# vescom.net
KiCad netlist of a schematic drawn in EAGLE
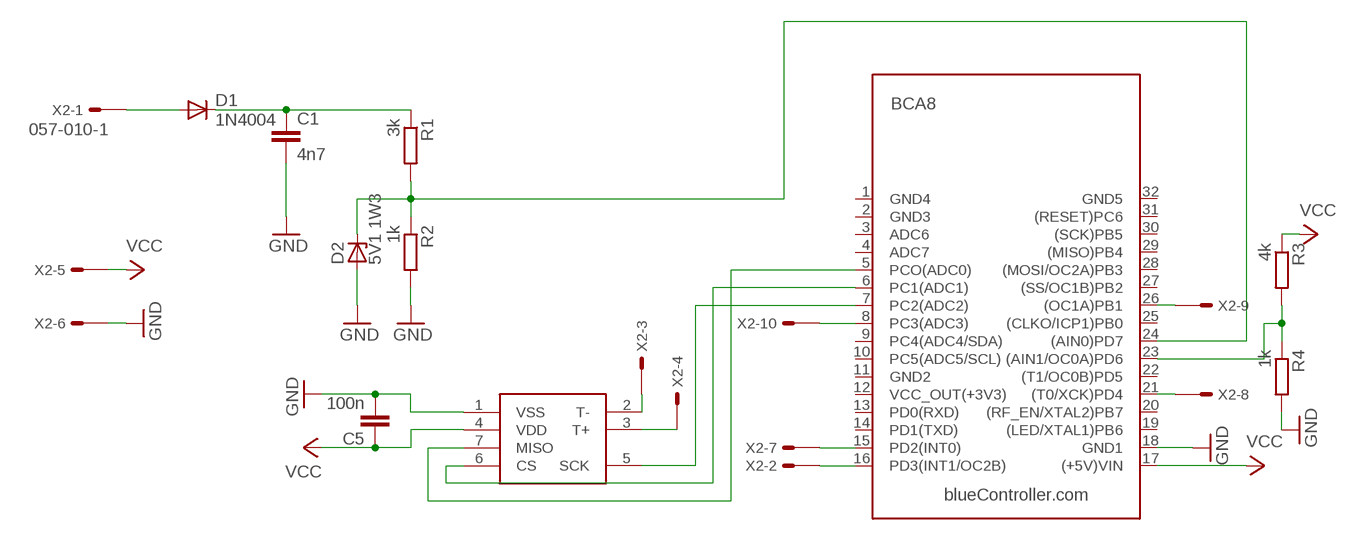
[diagram p0: schematic, sheet 1]

(export (version "E")
  (design (tool "Eeschema 10.0.6"))
  (components
    (comp (ref "C1")
      (value "4n7")
      (footprint "eagle-import:C025-025X050")
      (libsource (lib "eagle-import") (part "C-EU025-025X050"))
    )
    (comp (ref "C5")
      (value "100n")
      (footprint "eagle-import:C025-025X050")
      (libsource (lib "eagle-import") (part "C-EU025-025X050"))
    )
    (comp (ref "D1")
      (value "1N4004")
      (footprint "eagle-import:DO41-10")
      (libsource (lib "eagle-import") (part "1N4004"))
    )
    (comp (ref "D2")
      (value "5V1 1W3")
      (footprint "eagle-import:DO34Z7")
      (libsource (lib "eagle-import") (part "ZENER-DIODEDO34-7"))
    )
    (comp (ref "MAX6675")
      (value "MAX6675")
      (footprint "eagle-import:SO08")
      (libsource (lib "eagle-import") (part "MAX6675"))
    )
    (comp (ref "R1")
      (value "3k")
      (footprint "eagle-import:0207_10")
      (libsource (lib "eagle-import") (part "R-EU_0207/10"))
    )
    (comp (ref "R2")
      (value "1k")
      (footprint "eagle-import:0207_10")
      (libsource (lib "eagle-import") (part "R-EU_0207/10"))
    )
    (comp (ref "R3")
      (value "4k")
      (footprint "eagle-import:0207_10")
      (libsource (lib "eagle-import") (part "R-EU_0207/10"))
    )
    (comp (ref "R4")
      (value "1k")
      (footprint "eagle-import:0207_10")
      (libsource (lib "eagle-import") (part "R-EU_0207/10"))
    )
    (comp (ref "U$1") (value "BC") (footprint "eagle-import:BC") (libsource (lib "eagle-import") (part "BC")))
    (comp (ref "X2")
      (value "057-010-1")
      (footprint "eagle-import:057-010-1")
      (libsource (lib "eagle-import") (part "057-010-1"))
    )
  )
  (nets
    (net (code "1") (name "GND") (class "Default")
      (node (ref "C1") (pin "2") (pinfunction "2_2") (pintype "passive"))
      (node (ref "C5") (pin "2") (pinfunction "2_2") (pintype "passive"))
      (node (ref "D2") (pin "A") (pinfunction "A_A") (pintype "passive"))
      (node (ref "MAX6675") (pin "1") (pinfunction "VSS_1") (pintype "bidirectional"))
      (node (ref "R2") (pin "2") (pinfunction "2_2") (pintype "passive"))
      (node (ref "R4") (pin "2") (pinfunction "2_2") (pintype "passive"))
      (node (ref "U$1") (pin "18") (pinfunction "GND1_18") (pintype "bidirectional"))
      (node (ref "X2") (pin "6") (pinfunction "S_6") (pintype "passive"))
    )
    (net (code "2") (name "Net-(C1-Pad1)") (class "Default")
      (node (ref "C1") (pin "1") (pinfunction "1_1") (pintype "passive"))
      (node (ref "D1") (pin "C") (pinfunction "C_C") (pintype "passive"))
      (node (ref "R1") (pin "1") (pinfunction "1_1") (pintype "passive"))
    )
    (net (code "3") (name "Net-(MAX6675-CS)") (class "Default")
      (node (ref "MAX6675") (pin "6") (pinfunction "CS_6") (pintype "bidirectional"))
      (node (ref "U$1") (pin "6") (pinfunction "PC1(ADC1)_6") (pintype "bidirectional"))
    )
    (net (code "4") (name "Net-(MAX6675-MISO)") (class "Default")
      (node (ref "MAX6675") (pin "7") (pinfunction "MISO_7") (pintype "bidirectional"))
      (node (ref "U$1") (pin "5") (pinfunction "PCO(ADC0)_5") (pintype "bidirectional"))
    )
    (net (code "5") (name "Net-(MAX6675-SCK)") (class "Default")
      (node (ref "MAX6675") (pin "5") (pinfunction "SCK_5") (pintype "bidirectional"))
      (node (ref "U$1") (pin "7") (pinfunction "PC2(ADC2)_7") (pintype "bidirectional"))
    )
    (net (code "6") (name "Net-(MAX6675-T+)") (class "Default")
      (node (ref "MAX6675") (pin "3") (pinfunction "T+_3") (pintype "bidirectional"))
      (node (ref "X2") (pin "4") (pinfunction "S_4") (pintype "passive"))
    )
    (net (code "7") (name "Net-(MAX6675-T-)") (class "Default")
      (node (ref "MAX6675") (pin "2") (pinfunction "T-_2") (pintype "bidirectional"))
      (node (ref "X2") (pin "3") (pinfunction "S_3") (pintype "passive"))
    )
    (net (code "8") (name "Net-(U$1-(AIN0)PD7)") (class "Default")
      (node (ref "D2") (pin "C") (pinfunction "C_C") (pintype "passive"))
      (node (ref "R1") (pin "2") (pinfunction "2_2") (pintype "passive"))
      (node (ref "R2") (pin "1") (pinfunction "1_1") (pintype "passive"))
      (node (ref "U$1") (pin "24") (pinfunction "(AIN0)PD7_24") (pintype "bidirectional"))
    )
    (net (code "9") (name "Net-(U$1-(AIN1{slash}OC0A)PD6)") (class "Default")
      (node (ref "R3") (pin "2") (pinfunction "2_2") (pintype "passive"))
      (node (ref "R4") (pin "1") (pinfunction "1_1") (pintype "passive"))
      (node (ref "U$1") (pin "23") (pinfunction "(AIN1/OC0A)PD6_23") (pintype "bidirectional"))
    )
    (net (code "10") (name "Net-(U$1-(OC1A)PB1)") (class "Default")
      (node (ref "U$1") (pin "26") (pinfunction "(OC1A)PB1_26") (pintype "bidirectional"))
      (node (ref "X2") (pin "9") (pinfunction "S_9") (pintype "passive"))
    )
    (net (code "11") (name "Net-(U$1-(T0{slash}XCK)PD4)") (class "Default")
      (node (ref "U$1") (pin "21") (pinfunction "(T0/XCK)PD4_21") (pintype "bidirectional"))
      (node (ref "X2") (pin "8") (pinfunction "S_8") (pintype "passive"))
    )
    (net (code "12") (name "Net-(U$1-PC3(ADC3))") (class "Default")
      (node (ref "U$1") (pin "8") (pinfunction "PC3(ADC3)_8") (pintype "bidirectional"))
      (node (ref "X2") (pin "10") (pinfunction "S_10") (pintype "passive"))
    )
    (net (code "13") (name "Net-(U$1-PD2(INT0))") (class "Default")
      (node (ref "U$1") (pin "15") (pinfunction "PD2(INT0)_15") (pintype "bidirectional"))
      (node (ref "X2") (pin "7") (pinfunction "S_7") (pintype "passive"))
    )
    (net (code "14") (name "Net-(U$1-PD3(INT1{slash}OC2B))") (class "Default")
      (node (ref "U$1") (pin "16") (pinfunction "PD3(INT1/OC2B)_16") (pintype "bidirectional"))
      (node (ref "X2") (pin "2") (pinfunction "S_2") (pintype "passive"))
    )
    (net (code "15") (name "Net-(X2A-S)") (class "Default")
      (node (ref "D1") (pin "A") (pinfunction "A_A") (pintype "passive"))
      (node (ref "X2") (pin "1") (pinfunction "S_1") (pintype "passive"))
    )
    (net (code "16") (name "VCC") (class "Default")
      (node (ref "C5") (pin "1") (pinfunction "1_1") (pintype "passive"))
      (node (ref "MAX6675") (pin "4") (pinfunction "VDD_4") (pintype "bidirectional"))
      (node (ref "R3") (pin "1") (pinfunction "1_1") (pintype "passive"))
      (node (ref "U$1") (pin "17") (pinfunction "(+5V)VIN_17") (pintype "bidirectional"))
      (node (ref "X2") (pin "5") (pinfunction "S_5") (pintype "passive"))
    )
    (net (code "17") (name "unconnected-(U$1-(CLKO{slash}ICP1)PB0-Pad25)") (class "Default")
      (node (ref "U$1") (pin "25") (pinfunction "(CLKO/ICP1)PB0_25") (pintype "bidirectional"))
    )
    (net (code "18") (name "unconnected-(U$1-(LED{slash}XTAL1)PB6-Pad19)") (class "Default")
      (node (ref "U$1") (pin "19") (pinfunction "(LED/XTAL1)PB6_19") (pintype "bidirectional"))
    )
    (net (code "19") (name "unconnected-(U$1-(MISO)PB4-Pad29)") (class "Default")
      (node (ref "U$1") (pin "29") (pinfunction "(MISO)PB4_29") (pintype "bidirectional"))
    )
    (net (code "20") (name "unconnected-(U$1-(MOSI{slash}OC2A)PB3-Pad28)") (class "Default")
      (node (ref "U$1") (pin "28") (pinfunction "(MOSI/OC2A)PB3_28") (pintype "bidirectional"))
    )
    (net (code "21") (name "unconnected-(U$1-(RESET)PC6-Pad31)") (class "Default")
      (node (ref "U$1") (pin "31") (pinfunction "(RESET)PC6_31") (pintype "bidirectional"))
    )
    (net (code "22") (name "unconnected-(U$1-(RF_EN{slash}XTAL2)PB7-Pad20)") (class "Default")
      (node (ref "U$1") (pin "20") (pinfunction "(RF_EN/XTAL2)PB7_20") (pintype "bidirectional"))
    )
    (net (code "23") (name "unconnected-(U$1-(SCK)PB5-Pad30)") (class "Default")
      (node (ref "U$1") (pin "30") (pinfunction "(SCK)PB5_30") (pintype "bidirectional"))
    )
    (net (code "24") (name "unconnected-(U$1-(SS{slash}OC1B)PB2-Pad27)") (class "Default")
      (node (ref "U$1") (pin "27") (pinfunction "(SS/OC1B)PB2_27") (pintype "bidirectional"))
    )
    (net (code "25") (name "unconnected-(U$1-(T1{slash}OC0B)PD5-Pad22)") (class "Default")
      (node (ref "U$1") (pin "22") (pinfunction "(T1/OC0B)PD5_22") (pintype "bidirectional"))
    )
    (net (code "26") (name "unconnected-(U$1-ADC6-Pad3)") (class "Default")
      (node (ref "U$1") (pin "3") (pinfunction "ADC6_3") (pintype "bidirectional"))
    )
    (net (code "27") (name "unconnected-(U$1-ADC7-Pad4)") (class "Default")
      (node (ref "U$1") (pin "4") (pinfunction "ADC7_4") (pintype "bidirectional"))
    )
    (net (code "28") (name "unconnected-(U$1-GND2-Pad11)") (class "Default")
      (node (ref "U$1") (pin "11") (pinfunction "GND2_11") (pintype "bidirectional"))
    )
    (net (code "29") (name "unconnected-(U$1-GND3-Pad2)") (class "Default")
      (node (ref "U$1") (pin "2") (pinfunction "GND3_2") (pintype "bidirectional"))
    )
    (net (code "30") (name "unconnected-(U$1-GND4-Pad1)") (class "Default")
      (node (ref "U$1") (pin "1") (pinfunction "GND4_1") (pintype "bidirectional"))
    )
    (net (code "31") (name "unconnected-(U$1-GND5-Pad32)") (class "Default")
      (node (ref "U$1") (pin "32") (pinfunction "GND5_32") (pintype "bidirectional"))
    )
    (net (code "32") (name "unconnected-(U$1-PC4(ADC4{slash}SDA)-Pad9)") (class "Default")
      (node (ref "U$1") (pin "9") (pinfunction "PC4(ADC4/SDA)_9") (pintype "bidirectional"))
    )
    (net (code "33") (name "unconnected-(U$1-PC5(ADC5{slash}SCL)-Pad10)") (class "Default")
      (node (ref "U$1") (pin "10") (pinfunction "PC5(ADC5/SCL)_10") (pintype "bidirectional"))
    )
    (net (code "34") (name "unconnected-(U$1-PD0(RXD)-Pad13)") (class "Default")
      (node (ref "U$1") (pin "13") (pinfunction "PD0(RXD)_13") (pintype "bidirectional"))
    )
    (net (code "35") (name "unconnected-(U$1-PD1(TXD)-Pad14)") (class "Default")
      (node (ref "U$1") (pin "14") (pinfunction "PD1(TXD)_14") (pintype "bidirectional"))
    )
    (net (code "36") (name "unconnected-(U$1-VCC_OUT(+3V3)-Pad12)") (class "Default")
      (node (ref "U$1") (pin "12") (pinfunction "VCC_OUT(+3V3)_12") (pintype "bidirectional"))
    )
  )
)
